# rpi2_lcd.net
KiCad netlist of a schematic drawn in EAGLE
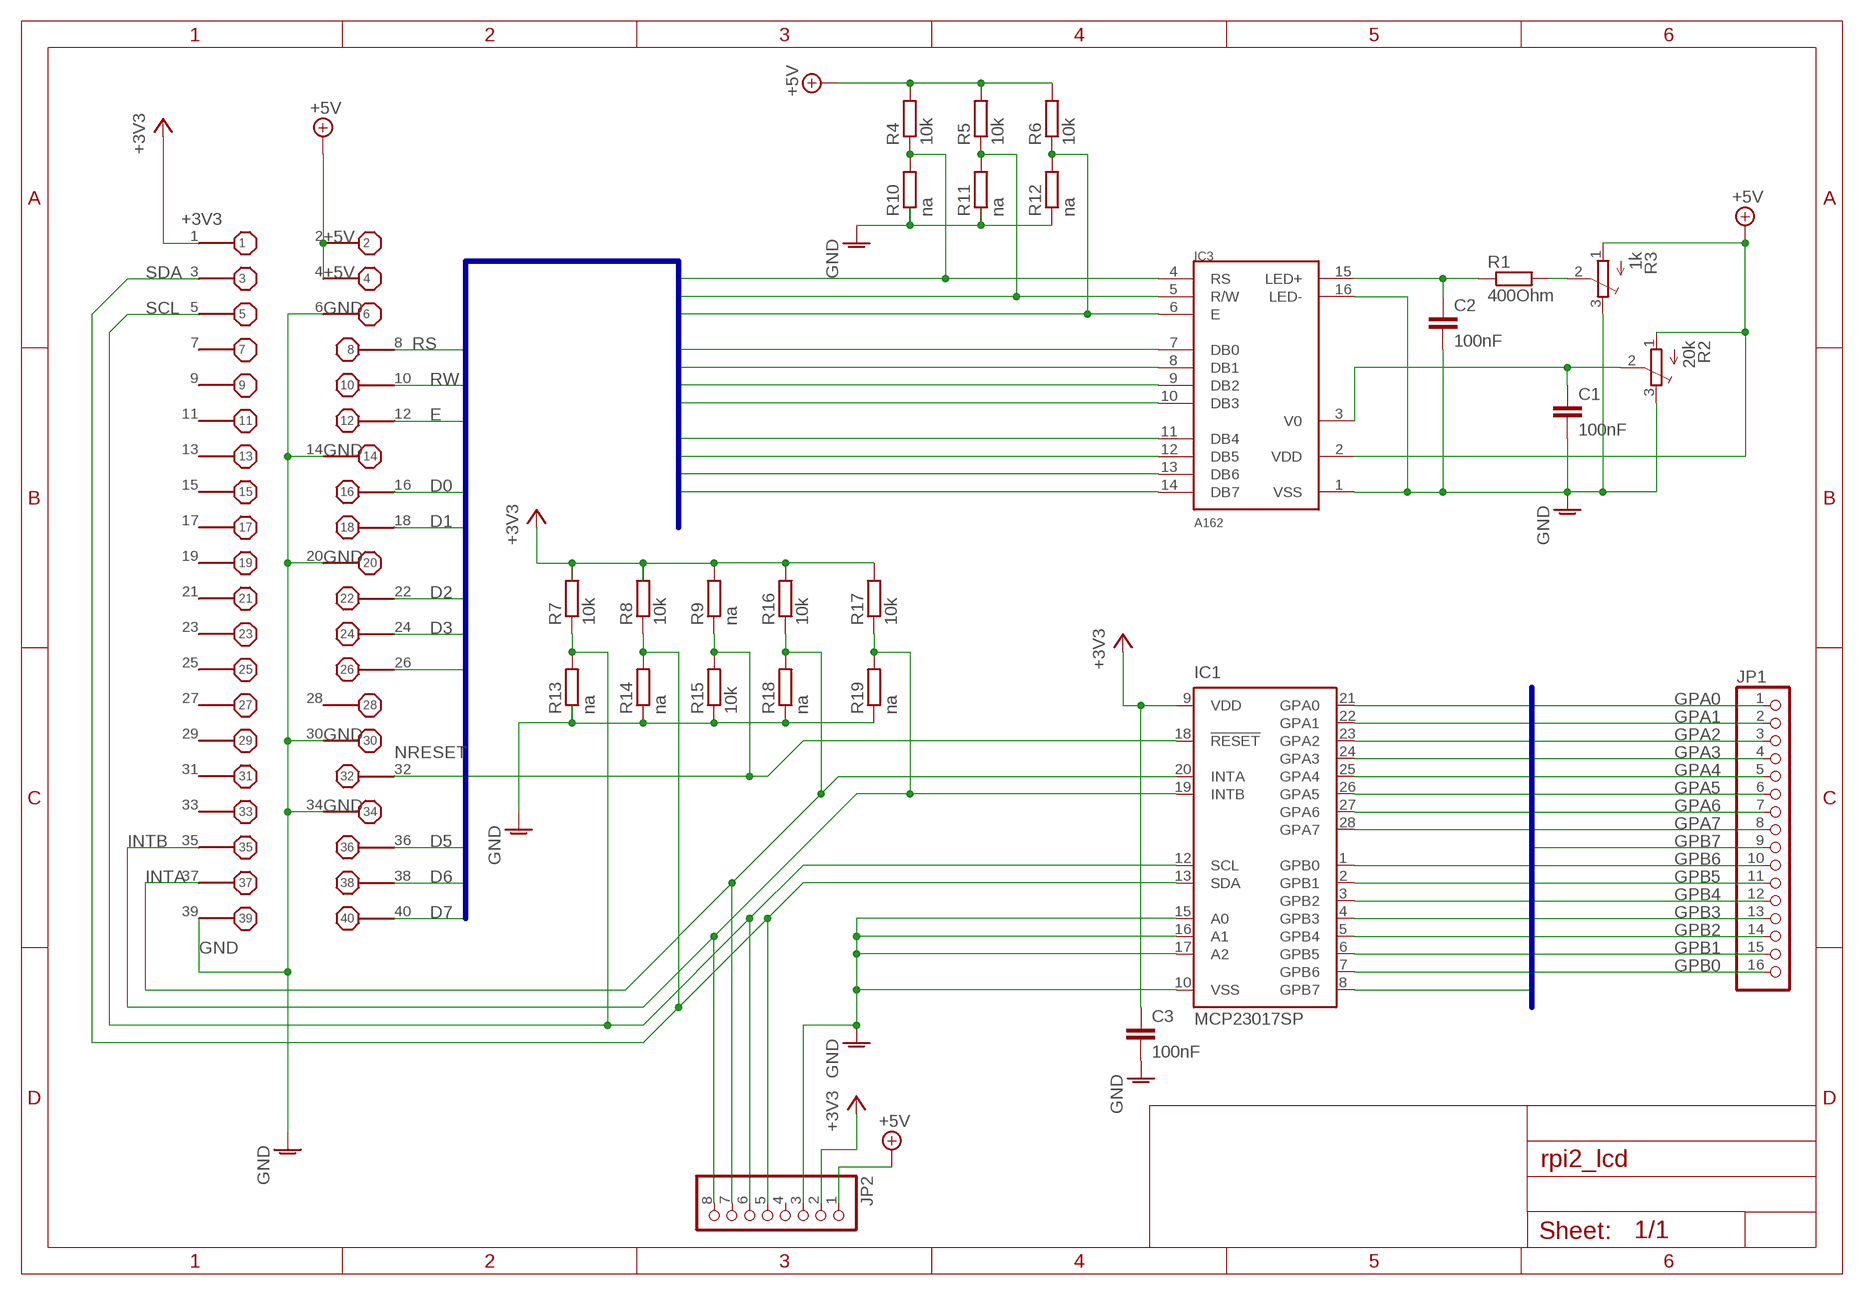
[diagram p0: schematic, sheet 1]

(export (version "E")
  (design (tool "Eeschema 10.0.6"))
  (components
    (comp (ref "C1")
      (value "100nF")
      (footprint "eagle-import:C0603")
      (libsource (lib "eagle-import") (part "C-EUC0603"))
    )
    (comp (ref "C2")
      (value "100nF")
      (footprint "eagle-import:C0603")
      (libsource (lib "eagle-import") (part "C-EUC0603"))
    )
    (comp (ref "C3")
      (value "100nF")
      (footprint "eagle-import:C0603")
      (libsource (lib "eagle-import") (part "C-EUC0603"))
    )
    (comp (ref "IC1")
      (value "MCP23017SP")
      (footprint "eagle-import:DIL28-3")
      (fields (field (name "MF") "MICROCHIP") (field (name "MPN") "MCP23017-E/SP"))
      (libsource (lib "eagle-import") (part "MCP23017SP"))
    )
    (comp (ref "IC3")
      (value "A162")
      (footprint "eagle-import:A162")
      (libsource (lib "eagle-import") (part "A162"))
    )
    (comp (ref "JP1")
      (value "PINHD-1X16")
      (footprint "eagle-import:1X16")
      (libsource (lib "eagle-import") (part "PINHD-1X16"))
    )
    (comp (ref "JP2")
      (value "PINHD-1X8")
      (footprint "eagle-import:1X08")
      (libsource (lib "eagle-import") (part "PINHD-1X8"))
    )
    (comp (ref "R1")
      (value "400Ohm")
      (footprint "eagle-import:R0603")
      (libsource (lib "eagle-import") (part "R-EU_R0603"))
    )
    (comp (ref "R2")
      (value "20k")
      (footprint "eagle-import:SM-42_43W")
      (libsource (lib "eagle-import") (part "TRIM_EU-SM-42/43W"))
    )
    (comp (ref "R3")
      (value "1k")
      (footprint "eagle-import:SM-42_43W")
      (libsource (lib "eagle-import") (part "TRIM_EU-SM-42/43W"))
    )
    (comp (ref "R4")
      (value "10k")
      (footprint "eagle-import:R0603")
      (libsource (lib "eagle-import") (part "R-EU_R0603"))
    )
    (comp (ref "R5")
      (value "10k")
      (footprint "eagle-import:R0603")
      (libsource (lib "eagle-import") (part "R-EU_R0603"))
    )
    (comp (ref "R6")
      (value "10k")
      (footprint "eagle-import:R0603")
      (libsource (lib "eagle-import") (part "R-EU_R0603"))
    )
    (comp (ref "R7")
      (value "10k")
      (footprint "eagle-import:R0603")
      (libsource (lib "eagle-import") (part "R-EU_R0603"))
    )
    (comp (ref "R8")
      (value "10k")
      (footprint "eagle-import:R0603")
      (libsource (lib "eagle-import") (part "R-EU_R0603"))
    )
    (comp (ref "R9")
      (value "na")
      (footprint "eagle-import:R0603")
      (libsource (lib "eagle-import") (part "R-EU_R0603"))
    )
    (comp (ref "R10")
      (value "na")
      (footprint "eagle-import:R0603")
      (libsource (lib "eagle-import") (part "R-EU_R0603"))
    )
    (comp (ref "R11")
      (value "na")
      (footprint "eagle-import:R0603")
      (libsource (lib "eagle-import") (part "R-EU_R0603"))
    )
    (comp (ref "R12")
      (value "na")
      (footprint "eagle-import:R0603")
      (libsource (lib "eagle-import") (part "R-EU_R0603"))
    )
    (comp (ref "R13")
      (value "na")
      (footprint "eagle-import:R0603")
      (libsource (lib "eagle-import") (part "R-EU_R0603"))
    )
    (comp (ref "R14")
      (value "na")
      (footprint "eagle-import:R0603")
      (libsource (lib "eagle-import") (part "R-EU_R0603"))
    )
    (comp (ref "R15")
      (value "10k")
      (footprint "eagle-import:R0603")
      (libsource (lib "eagle-import") (part "R-EU_R0603"))
    )
    (comp (ref "R16")
      (value "10k")
      (footprint "eagle-import:R0603")
      (libsource (lib "eagle-import") (part "R-EU_R0603"))
    )
    (comp (ref "R17")
      (value "10k")
      (footprint "eagle-import:R0603")
      (libsource (lib "eagle-import") (part "R-EU_R0603"))
    )
    (comp (ref "R18")
      (value "na")
      (footprint "eagle-import:R0603")
      (libsource (lib "eagle-import") (part "R-EU_R0603"))
    )
    (comp (ref "R19")
      (value "na")
      (footprint "eagle-import:R0603")
      (libsource (lib "eagle-import") (part "R-EU_R0603"))
    )
    (comp (ref "X1")
      (value "B+_GPIO")
      (footprint "eagle-import:B+_GPIO")
      (libsource (lib "eagle-import") (part "B+_GPIO"))
    )
  )
  (nets
    (net (code "1") (name "+3V3") (class "Default")
      (node (ref "C3") (pin "1") (pinfunction "1_1") (pintype "passive"))
      (node (ref "IC1") (pin "9") (pinfunction "VDD_9") (pintype "power_in"))
      (node (ref "JP2") (pin "2") (pinfunction "2_2") (pintype "passive"))
      (node (ref "R16") (pin "2") (pinfunction "2_2") (pintype "passive"))
      (node (ref "R17") (pin "2") (pinfunction "2_2") (pintype "passive"))
      (node (ref "R7") (pin "2") (pinfunction "2_2") (pintype "passive"))
      (node (ref "R8") (pin "2") (pinfunction "2_2") (pintype "passive"))
      (node (ref "R9") (pin "2") (pinfunction "2_2") (pintype "passive"))
      (node (ref "X1") (pin "1") (pinfunction "P$1_1") (pintype "bidirectional"))
    )
    (net (code "2") (name "+5V") (class "Default")
      (node (ref "IC3") (pin "2") (pinfunction "VDD_2") (pintype "bidirectional"))
      (node (ref "JP2") (pin "1") (pinfunction "1_1") (pintype "passive"))
      (node (ref "R2") (pin "1") (pinfunction "A_1") (pintype "passive"))
      (node (ref "R3") (pin "1") (pinfunction "A_1") (pintype "passive"))
      (node (ref "R4") (pin "2") (pinfunction "2_2") (pintype "passive"))
      (node (ref "R5") (pin "2") (pinfunction "2_2") (pintype "passive"))
      (node (ref "R6") (pin "2") (pinfunction "2_2") (pintype "passive"))
      (node (ref "X1") (pin "2") (pinfunction "P$1_2") (pintype "bidirectional"))
      (node (ref "X1") (pin "4") (pinfunction "P$1_4") (pintype "bidirectional"))
    )
    (net (code "3") (name "/D0") (class "Default")
      (node (ref "IC3") (pin "7") (pinfunction "DB0_7") (pintype "bidirectional"))
      (node (ref "X1") (pin "16") (pinfunction "P$1_16") (pintype "bidirectional"))
    )
    (net (code "4") (name "/D1") (class "Default")
      (node (ref "IC3") (pin "8") (pinfunction "DB1_8") (pintype "bidirectional"))
      (node (ref "X1") (pin "18") (pinfunction "P$1_18") (pintype "bidirectional"))
    )
    (net (code "5") (name "/D2") (class "Default")
      (node (ref "IC3") (pin "9") (pinfunction "DB2_9") (pintype "bidirectional"))
      (node (ref "X1") (pin "22") (pinfunction "P$1_22") (pintype "bidirectional"))
    )
    (net (code "6") (name "/D3") (class "Default")
      (node (ref "IC3") (pin "10") (pinfunction "DB3_10") (pintype "bidirectional"))
      (node (ref "X1") (pin "24") (pinfunction "P$1_24") (pintype "bidirectional"))
    )
    (net (code "7") (name "/D4") (class "Default")
      (node (ref "IC3") (pin "11") (pinfunction "DB4_11") (pintype "bidirectional"))
      (node (ref "X1") (pin "26") (pinfunction "P$1_26") (pintype "bidirectional"))
    )
    (net (code "8") (name "/D5") (class "Default")
      (node (ref "IC3") (pin "12") (pinfunction "DB5_12") (pintype "bidirectional"))
      (node (ref "X1") (pin "36") (pinfunction "P$1_36") (pintype "bidirectional"))
    )
    (net (code "9") (name "/D6") (class "Default")
      (node (ref "IC3") (pin "13") (pinfunction "DB6_13") (pintype "bidirectional"))
      (node (ref "X1") (pin "38") (pinfunction "P$1_38") (pintype "bidirectional"))
    )
    (net (code "10") (name "/D7") (class "Default")
      (node (ref "IC3") (pin "14") (pinfunction "DB7_14") (pintype "bidirectional"))
      (node (ref "X1") (pin "40") (pinfunction "P$1_40") (pintype "bidirectional"))
    )
    (net (code "11") (name "/E") (class "Default")
      (node (ref "IC3") (pin "6") (pinfunction "E_6") (pintype "bidirectional"))
      (node (ref "R12") (pin "2") (pinfunction "2_2") (pintype "passive"))
      (node (ref "R6") (pin "1") (pinfunction "1_1") (pintype "passive"))
      (node (ref "X1") (pin "12") (pinfunction "P$1_12") (pintype "bidirectional"))
    )
    (net (code "12") (name "/GPA0") (class "Default")
      (node (ref "IC1") (pin "21") (pinfunction "GPA0_21") (pintype "bidirectional"))
      (node (ref "JP1") (pin "1") (pinfunction "1_1") (pintype "passive"))
    )
    (net (code "13") (name "/GPA1") (class "Default")
      (node (ref "IC1") (pin "22") (pinfunction "GPA1_22") (pintype "bidirectional"))
      (node (ref "JP1") (pin "2") (pinfunction "2_2") (pintype "passive"))
    )
    (net (code "14") (name "/GPA2") (class "Default")
      (node (ref "IC1") (pin "23") (pinfunction "GPA2_23") (pintype "bidirectional"))
      (node (ref "JP1") (pin "3") (pinfunction "3_3") (pintype "passive"))
    )
    (net (code "15") (name "/GPA3") (class "Default")
      (node (ref "IC1") (pin "24") (pinfunction "GPA3_24") (pintype "bidirectional"))
      (node (ref "JP1") (pin "4") (pinfunction "4_4") (pintype "passive"))
    )
    (net (code "16") (name "/GPA4") (class "Default")
      (node (ref "IC1") (pin "25") (pinfunction "GPA4_25") (pintype "bidirectional"))
      (node (ref "JP1") (pin "5") (pinfunction "5_5") (pintype "passive"))
    )
    (net (code "17") (name "/GPA5") (class "Default")
      (node (ref "IC1") (pin "26") (pinfunction "GPA5_26") (pintype "bidirectional"))
      (node (ref "JP1") (pin "6") (pinfunction "6_6") (pintype "passive"))
    )
    (net (code "18") (name "/GPA6") (class "Default")
      (node (ref "IC1") (pin "27") (pinfunction "GPA6_27") (pintype "bidirectional"))
      (node (ref "JP1") (pin "7") (pinfunction "7_7") (pintype "passive"))
    )
    (net (code "19") (name "/GPA7") (class "Default")
      (node (ref "IC1") (pin "28") (pinfunction "GPA7_28") (pintype "bidirectional"))
      (node (ref "JP1") (pin "8") (pinfunction "8_8") (pintype "passive"))
    )
    (net (code "20") (name "/GPB0") (class "Default")
      (node (ref "IC1") (pin "1") (pinfunction "GPB0_1") (pintype "bidirectional"))
      (node (ref "JP1") (pin "16") (pinfunction "16_16") (pintype "passive"))
    )
    (net (code "21") (name "/GPB1") (class "Default")
      (node (ref "IC1") (pin "2") (pinfunction "GPB1_2") (pintype "bidirectional"))
      (node (ref "JP1") (pin "15") (pinfunction "15_15") (pintype "passive"))
    )
    (net (code "22") (name "/GPB2") (class "Default")
      (node (ref "IC1") (pin "3") (pinfunction "GPB2_3") (pintype "bidirectional"))
      (node (ref "JP1") (pin "14") (pinfunction "14_14") (pintype "passive"))
    )
    (net (code "23") (name "/GPB3") (class "Default")
      (node (ref "IC1") (pin "4") (pinfunction "GPB3_4") (pintype "bidirectional"))
      (node (ref "JP1") (pin "13") (pinfunction "13_13") (pintype "passive"))
    )
    (net (code "24") (name "/GPB4") (class "Default")
      (node (ref "IC1") (pin "5") (pinfunction "GPB4_5") (pintype "bidirectional"))
      (node (ref "JP1") (pin "12") (pinfunction "12_12") (pintype "passive"))
    )
    (net (code "25") (name "/GPB5") (class "Default")
      (node (ref "IC1") (pin "6") (pinfunction "GPB5_6") (pintype "bidirectional"))
      (node (ref "JP1") (pin "11") (pinfunction "11_11") (pintype "passive"))
    )
    (net (code "26") (name "/GPB6") (class "Default")
      (node (ref "IC1") (pin "7") (pinfunction "GPB6_7") (pintype "bidirectional"))
      (node (ref "JP1") (pin "10") (pinfunction "10_10") (pintype "passive"))
    )
    (net (code "27") (name "/GPB7") (class "Default")
      (node (ref "IC1") (pin "8") (pinfunction "GPB7_8") (pintype "bidirectional"))
      (node (ref "JP1") (pin "9") (pinfunction "9_9") (pintype "passive"))
    )
    (net (code "28") (name "/INTA") (class "Default")
      (node (ref "IC1") (pin "20") (pinfunction "INTA_20") (pintype "output"))
      (node (ref "JP2") (pin "7") (pinfunction "7_7") (pintype "passive"))
      (node (ref "R16") (pin "1") (pinfunction "1_1") (pintype "passive"))
      (node (ref "R18") (pin "2") (pinfunction "2_2") (pintype "passive"))
      (node (ref "X1") (pin "37") (pinfunction "P$1_37") (pintype "bidirectional"))
    )
    (net (code "29") (name "/INTB") (class "Default")
      (node (ref "IC1") (pin "19") (pinfunction "INTB_19") (pintype "output"))
      (node (ref "JP2") (pin "8") (pinfunction "8_8") (pintype "passive"))
      (node (ref "R17") (pin "1") (pinfunction "1_1") (pintype "passive"))
      (node (ref "R19") (pin "2") (pinfunction "2_2") (pintype "passive"))
      (node (ref "X1") (pin "35") (pinfunction "P$1_35") (pintype "bidirectional"))
    )
    (net (code "30") (name "/NRESET") (class "Default")
      (node (ref "IC1") (pin "18") (pinfunction "~{RESET}_18") (pintype "input"))
      (node (ref "R15") (pin "2") (pinfunction "2_2") (pintype "passive"))
      (node (ref "R9") (pin "1") (pinfunction "1_1") (pintype "passive"))
      (node (ref "X1") (pin "32") (pinfunction "P$1_32") (pintype "bidirectional"))
    )
    (net (code "31") (name "/RS") (class "Default")
      (node (ref "IC3") (pin "4") (pinfunction "RS_4") (pintype "bidirectional"))
      (node (ref "R10") (pin "2") (pinfunction "2_2") (pintype "passive"))
      (node (ref "R4") (pin "1") (pinfunction "1_1") (pintype "passive"))
      (node (ref "X1") (pin "8") (pinfunction "P$1_8") (pintype "bidirectional"))
    )
    (net (code "32") (name "/RW") (class "Default")
      (node (ref "IC3") (pin "5") (pinfunction "R/W_5") (pintype "bidirectional"))
      (node (ref "R11") (pin "2") (pinfunction "2_2") (pintype "passive"))
      (node (ref "R5") (pin "1") (pinfunction "1_1") (pintype "passive"))
      (node (ref "X1") (pin "10") (pinfunction "P$1_10") (pintype "bidirectional"))
    )
    (net (code "33") (name "/SCL") (class "Default")
      (node (ref "IC1") (pin "12") (pinfunction "SCL_12") (pintype "input"))
      (node (ref "JP2") (pin "6") (pinfunction "6_6") (pintype "passive"))
      (node (ref "R13") (pin "2") (pinfunction "2_2") (pintype "passive"))
      (node (ref "R7") (pin "1") (pinfunction "1_1") (pintype "passive"))
      (node (ref "X1") (pin "5") (pinfunction "P$1_5") (pintype "bidirectional"))
    )
    (net (code "34") (name "/SDA") (class "Default")
      (node (ref "IC1") (pin "13") (pinfunction "SDA_13") (pintype "bidirectional"))
      (node (ref "JP2") (pin "5") (pinfunction "5_5") (pintype "passive"))
      (node (ref "R14") (pin "2") (pinfunction "2_2") (pintype "passive"))
      (node (ref "R8") (pin "1") (pinfunction "1_1") (pintype "passive"))
      (node (ref "X1") (pin "3") (pinfunction "P$1_3") (pintype "bidirectional"))
    )
    (net (code "35") (name "GND") (class "Default")
      (node (ref "C1") (pin "2") (pinfunction "2_2") (pintype "passive"))
      (node (ref "C2") (pin "2") (pinfunction "2_2") (pintype "passive"))
      (node (ref "C3") (pin "2") (pinfunction "2_2") (pintype "passive"))
      (node (ref "IC1") (pin "10") (pinfunction "VSS_10") (pintype "power_in"))
      (node (ref "IC1") (pin "15") (pinfunction "A0_15") (pintype "input"))
      (node (ref "IC1") (pin "16") (pinfunction "A1_16") (pintype "input"))
      (node (ref "IC1") (pin "17") (pinfunction "A2_17") (pintype "input"))
      (node (ref "IC3") (pin "1") (pinfunction "VSS_1") (pintype "bidirectional"))
      (node (ref "IC3") (pin "16") (pinfunction "LED-_16") (pintype "bidirectional"))
      (node (ref "JP2") (pin "3") (pinfunction "3_3") (pintype "passive"))
      (node (ref "R10") (pin "1") (pinfunction "1_1") (pintype "passive"))
      (node (ref "R11") (pin "1") (pinfunction "1_1") (pintype "passive"))
      (node (ref "R12") (pin "1") (pinfunction "1_1") (pintype "passive"))
      (node (ref "R13") (pin "1") (pinfunction "1_1") (pintype "passive"))
      (node (ref "R14") (pin "1") (pinfunction "1_1") (pintype "passive"))
      (node (ref "R15") (pin "1") (pinfunction "1_1") (pintype "passive"))
      (node (ref "R18") (pin "1") (pinfunction "1_1") (pintype "passive"))
      (node (ref "R19") (pin "1") (pinfunction "1_1") (pintype "passive"))
      (node (ref "R2") (pin "3") (pinfunction "E_3") (pintype "passive"))
      (node (ref "R3") (pin "3") (pinfunction "E_3") (pintype "passive"))
      (node (ref "X1") (pin "14") (pinfunction "P$1_14") (pintype "bidirectional"))
      (node (ref "X1") (pin "20") (pinfunction "P$1_20") (pintype "bidirectional"))
      (node (ref "X1") (pin "30") (pinfunction "P$1_30") (pintype "bidirectional"))
      (node (ref "X1") (pin "34") (pinfunction "P$1_34") (pintype "bidirectional"))
      (node (ref "X1") (pin "39") (pinfunction "P$1_39") (pintype "bidirectional"))
      (node (ref "X1") (pin "6") (pinfunction "P$1_6") (pintype "bidirectional"))
    )
    (net (code "36") (name "Net-(IC3-LED+)") (class "Default")
      (node (ref "C2") (pin "1") (pinfunction "1_1") (pintype "passive"))
      (node (ref "IC3") (pin "15") (pinfunction "LED+_15") (pintype "bidirectional"))
      (node (ref "R1") (pin "1") (pinfunction "1_1") (pintype "passive"))
    )
    (net (code "37") (name "Net-(IC3-V0)") (class "Default")
      (node (ref "C1") (pin "1") (pinfunction "1_1") (pintype "passive"))
      (node (ref "IC3") (pin "3") (pinfunction "V0_3") (pintype "bidirectional"))
      (node (ref "R2") (pin "2") (pinfunction "S_2") (pintype "passive"))
    )
    (net (code "38") (name "Net-(R3-S)") (class "Default")
      (node (ref "R1") (pin "2") (pinfunction "2_2") (pintype "passive"))
      (node (ref "R3") (pin "2") (pinfunction "S_2") (pintype "passive"))
    )
    (net (code "39") (name "unconnected-(JP2-Pad4)") (class "Default")
      (node (ref "JP2") (pin "4") (pinfunction "4_4") (pintype "passive"))
    )
    (net (code "40") (name "unconnected-(X1AA-P$1-Pad33)") (class "Default")
      (node (ref "X1") (pin "33") (pinfunction "P$1_33") (pintype "bidirectional"))
    )
    (net (code "41") (name "unconnected-(X1AL-P$1-Pad7)") (class "Default")
      (node (ref "X1") (pin "7") (pinfunction "P$1_7") (pintype "bidirectional"))
    )
    (net (code "42") (name "unconnected-(X1AN-P$1-Pad9)") (class "Default")
      (node (ref "X1") (pin "9") (pinfunction "P$1_9") (pintype "bidirectional"))
    )
    (net (code "43") (name "unconnected-(X1C-P$1-Pad11)") (class "Default")
      (node (ref "X1") (pin "11") (pinfunction "P$1_11") (pintype "bidirectional"))
    )
    (net (code "44") (name "unconnected-(X1E-P$1-Pad13)") (class "Default")
      (node (ref "X1") (pin "13") (pinfunction "P$1_13") (pintype "bidirectional"))
    )
    (net (code "45") (name "unconnected-(X1G-P$1-Pad15)") (class "Default")
      (node (ref "X1") (pin "15") (pinfunction "P$1_15") (pintype "bidirectional"))
    )
    (net (code "46") (name "unconnected-(X1I-P$1-Pad17)") (class "Default")
      (node (ref "X1") (pin "17") (pinfunction "P$1_17") (pintype "bidirectional"))
    )
    (net (code "47") (name "unconnected-(X1K-P$1-Pad19)") (class "Default")
      (node (ref "X1") (pin "19") (pinfunction "P$1_19") (pintype "bidirectional"))
    )
    (net (code "48") (name "unconnected-(X1N-P$1-Pad21)") (class "Default")
      (node (ref "X1") (pin "21") (pinfunction "P$1_21") (pintype "bidirectional"))
    )
    (net (code "49") (name "unconnected-(X1P-P$1-Pad23)") (class "Default")
      (node (ref "X1") (pin "23") (pinfunction "P$1_23") (pintype "bidirectional"))
    )
    (net (code "50") (name "unconnected-(X1R-P$1-Pad25)") (class "Default")
      (node (ref "X1") (pin "25") (pinfunction "P$1_25") (pintype "bidirectional"))
    )
    (net (code "51") (name "unconnected-(X1T-P$1-Pad27)") (class "Default")
      (node (ref "X1") (pin "27") (pinfunction "P$1_27") (pintype "bidirectional"))
    )
    (net (code "52") (name "unconnected-(X1U-P$1-Pad28)") (class "Default")
      (node (ref "X1") (pin "28") (pinfunction "P$1_28") (pintype "bidirectional"))
    )
    (net (code "53") (name "unconnected-(X1V-P$1-Pad29)") (class "Default")
      (node (ref "X1") (pin "29") (pinfunction "P$1_29") (pintype "bidirectional"))
    )
    (net (code "54") (name "unconnected-(X1Y-P$1-Pad31)") (class "Default")
      (node (ref "X1") (pin "31") (pinfunction "P$1_31") (pintype "bidirectional"))
    )
  )
)
